# Sheet1.net
KiCad netlist of a schematic drawn in Altium Designer
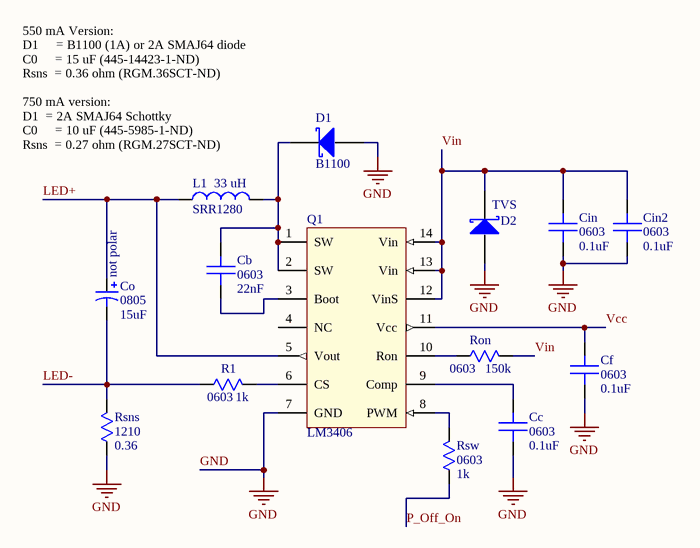
[diagram p0: Sheet1.SchDoc]

(export (version "E")
  (design (tool "Eeschema 10.0.6"))
  (components
    (comp (ref "Cb")
      (value "0603")
      (footprint "0603")
      (description "0603 capacitor")
      (fields (field (name "ALTIUM_VALUE") "22nF"))
      (libsource (lib "NewLibrary") (part "Capacitor"))
    )
    (comp (ref "Cc")
      (value "0603")
      (footprint "0603")
      (description "0603 capacitor")
      (fields (field (name "ALTIUM_VALUE") "0.1uF"))
      (libsource (lib "NewLibrary") (part "Capacitor"))
    )
    (comp (ref "Cf")
      (value "0603")
      (footprint "0603")
      (description "0603 capacitor")
      (fields (field (name "ALTIUM_VALUE") "0.1uF"))
      (libsource (lib "NewLibrary") (part "Capacitor"))
    )
    (comp (ref "Cin")
      (value "0603")
      (footprint "0603")
      (description "0603 capacitor")
      (fields (field (name "ALTIUM_VALUE") "0.1uF"))
      (libsource (lib "NewLibrary") (part "Capacitor"))
    )
    (comp (ref "Cin2")
      (value "0603")
      (footprint "0603")
      (description "0603 capacitor")
      (fields (field (name "ALTIUM_VALUE") "0.1uF"))
      (libsource (lib "NewLibrary") (part "Capacitor"))
    )
    (comp (ref "Co")
      (value "0805")
      (footprint "C0805")
      (description "Polarized Capacitor (Surface Mount)")
      (fields (field (name "ALTIUM_VALUE") "15uF") (field (name "PUBLISHER") "Altium Limited"))
      (libsource (lib "Miscellaneous Devices") (part "Cap Pol3"))
    )
    (comp (ref "D1")
      (value "B1100")
      (footprint "Diode-B1100-SMA")
      (libsource (lib "NewLibrary") (part "Diode - B1100"))
    )
    (comp (ref "D2")
      (value "B1100")
      (footprint "Diode-B1100-SMA")
      (libsource (lib "NewLibrary") (part "Diode - B1100"))
    )
    (comp (ref "L1")
      (value "SRR1280")
      (footprint "SRR1280-inductor")
      (libsource (lib "NewLibrary") (part "Inductor - SRR1280"))
    )
    (comp (ref "Q1")
      (value "LM3406")
      (footprint "TSSOP-14")
      (description "1.5A - LED Driver")
      (libsource (lib "NewLibrary") (part "LM3406"))
    )
    (comp (ref "R1")
      (value "0603")
      (footprint "0603")
      (description "0603 resistor")
      (fields (field (name "ALTIUM_VALUE") "1k"))
      (libsource (lib "NewLibrary") (part "Resistor"))
    )
    (comp (ref "Ron")
      (value "0603")
      (footprint "0603")
      (description "0603 resistor")
      (fields (field (name "ALTIUM_VALUE") "150k"))
      (libsource (lib "NewLibrary") (part "Resistor"))
    )
    (comp (ref "Rsns")
      (value "1210")
      (footprint "1210")
      (description "1210 resistor")
      (fields (field (name "ALTIUM_VALUE") "0.36"))
      (libsource (lib "NewLibrary") (part "Resistor_1210"))
    )
    (comp (ref "Rsw")
      (value "0603")
      (footprint "0603")
      (description "0603 resistor")
      (fields (field (name "ALTIUM_VALUE") "1k"))
      (libsource (lib "NewLibrary") (part "Resistor"))
    )
  )
  (nets
    (net (code "1") (name "/LED+") (class "Default")
      (node (ref "Co") (pin "1") (pinfunction "1_1") (pintype "passive"))
      (node (ref "L1") (pin "1") (pinfunction "1_1") (pintype "passive"))
      (node (ref "Q1") (pin "5") (pinfunction "Vout_5") (pintype "output"))
    )
    (net (code "2") (name "/LED-") (class "Default")
      (node (ref "Co") (pin "2") (pinfunction "2_2") (pintype "passive"))
      (node (ref "R1") (pin "1") (pinfunction "1_1") (pintype "passive"))
      (node (ref "Rsns") (pin "2") (pinfunction "2_2") (pintype "passive"))
    )
    (net (code "3") (name "/P_Off_On") (class "Default")
      (node (ref "Rsw") (pin "1") (pinfunction "1_1") (pintype "passive"))
    )
    (net (code "4") (name "/Vcc") (class "Default")
      (node (ref "Cf") (pin "2") (pinfunction "2_2") (pintype "passive"))
      (node (ref "Q1") (pin "11") (pinfunction "Vcc_11") (pintype "output"))
    )
    (net (code "5") (name "/Vin") (class "Default")
      (node (ref "Cin") (pin "2") (pinfunction "2_2") (pintype "passive"))
      (node (ref "Cin2") (pin "2") (pinfunction "2_2") (pintype "passive"))
      (node (ref "D2") (pin "2") (pinfunction "K_2") (pintype "passive"))
      (node (ref "Q1") (pin "12") (pinfunction "VinS_12") (pintype "passive"))
      (node (ref "Q1") (pin "13") (pinfunction "Vin_13") (pintype "input"))
      (node (ref "Q1") (pin "14") (pinfunction "Vin_14") (pintype "input"))
      (node (ref "Ron") (pin "2") (pinfunction "2_2") (pintype "passive"))
    )
    (net (code "6") (name "GND") (class "Default")
      (node (ref "Cc") (pin "1") (pinfunction "1_1") (pintype "passive"))
      (node (ref "Cf") (pin "1") (pinfunction "1_1") (pintype "passive"))
      (node (ref "Cin") (pin "1") (pinfunction "1_1") (pintype "passive"))
      (node (ref "Cin2") (pin "1") (pinfunction "1_1") (pintype "passive"))
      (node (ref "D1") (pin "1") (pinfunction "A_1") (pintype "passive"))
      (node (ref "D2") (pin "1") (pinfunction "A_1") (pintype "passive"))
      (node (ref "Q1") (pin "7") (pinfunction "GND_7") (pintype "power_in"))
      (node (ref "Rsns") (pin "1") (pinfunction "1_1") (pintype "passive"))
    )
    (net (code "7") (name "Net-(D1-K)") (class "Default")
      (node (ref "Cb") (pin "2") (pinfunction "2_2") (pintype "passive"))
      (node (ref "D1") (pin "2") (pinfunction "K_2") (pintype "passive"))
      (node (ref "L1") (pin "2") (pinfunction "2_2") (pintype "passive"))
      (node (ref "Q1") (pin "1") (pinfunction "SW_1") (pintype "passive"))
      (node (ref "Q1") (pin "2") (pinfunction "SW_2") (pintype "passive"))
    )
    (net (code "8") (name "Net-(Q1-Boot)") (class "Default")
      (node (ref "Cb") (pin "1") (pinfunction "1_1") (pintype "passive"))
      (node (ref "Q1") (pin "3") (pinfunction "Boot_3") (pintype "passive"))
    )
    (net (code "9") (name "Net-(Q1-CS)") (class "Default")
      (node (ref "Q1") (pin "6") (pinfunction "CS_6") (pintype "passive"))
      (node (ref "R1") (pin "2") (pinfunction "2_2") (pintype "passive"))
    )
    (net (code "10") (name "Net-(Q1-Comp)") (class "Default")
      (node (ref "Cc") (pin "2") (pinfunction "2_2") (pintype "passive"))
      (node (ref "Q1") (pin "9") (pinfunction "Comp_9") (pintype "passive"))
    )
    (net (code "11") (name "Net-(Q1-PWM)") (class "Default")
      (node (ref "Q1") (pin "8") (pinfunction "PWM_8") (pintype "input"))
      (node (ref "Rsw") (pin "2") (pinfunction "2_2") (pintype "passive"))
    )
    (net (code "12") (name "Net-(Q1-Ron)") (class "Default")
      (node (ref "Q1") (pin "10") (pinfunction "Ron_10") (pintype "passive"))
      (node (ref "Ron") (pin "1") (pinfunction "1_1") (pintype "passive"))
    )
    (net (code "13") (name "unconnected-(Q1-NC-Pad4)") (class "Default")
      (node (ref "Q1") (pin "4") (pinfunction "NC_4") (pintype "passive"))
    )
  )
)
